# BLE_v0_1a_prater_mod.net
KiCad netlist of a schematic drawn in EAGLE
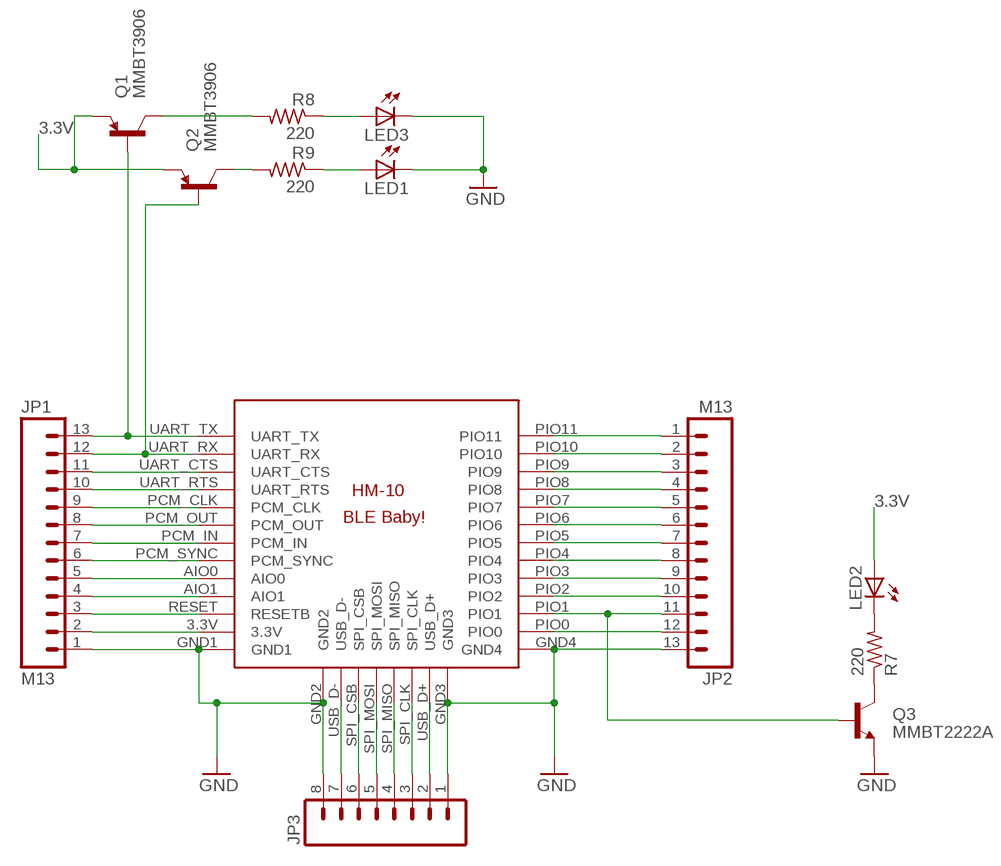
[diagram p0: schematic, sheet 1]

(export (version "E")
  (design (tool "Eeschema 10.0.6"))
  (components
    (comp (ref "JP1")
      (value "M13")
      (footprint "eagle-import:1X13")
      (libsource (lib "eagle-import") (part "M13"))
    )
    (comp (ref "JP2")
      (value "M13")
      (footprint "eagle-import:1X13")
      (libsource (lib "eagle-import") (part "M13"))
    )
    (comp (ref "JP3")
      (value "M081X08")
      (footprint "eagle-import:1X08")
      (libsource (lib "eagle-import") (part "M081X08"))
    )
    (comp (ref "LED1")
      (value "LED0603")
      (footprint "eagle-import:LED-0603")
      (libsource (lib "eagle-import") (part "LED0603"))
    )
    (comp (ref "LED2")
      (value "LED0603")
      (footprint "eagle-import:LED-0603")
      (libsource (lib "eagle-import") (part "LED0603"))
    )
    (comp (ref "LED3")
      (value "LED0603")
      (footprint "eagle-import:LED-0603")
      (libsource (lib "eagle-import") (part "LED0603"))
    )
    (comp (ref "Q1")
      (value "MMBT3906")
      (footprint "eagle-import:SOT23")
      (libsource (lib "eagle-import") (part "TRANSISTOR_PNPMMBT3906"))
    )
    (comp (ref "Q2")
      (value "MMBT3906")
      (footprint "eagle-import:SOT23")
      (libsource (lib "eagle-import") (part "TRANSISTOR_PNPMMBT3906"))
    )
    (comp (ref "Q3")
      (value "MMBT2222A")
      (footprint "eagle-import:SOT23")
      (libsource (lib "eagle-import") (part "TRANSISTOR_NPNMMBT2222A"))
    )
    (comp (ref "R7")
      (value "220")
      (footprint "eagle-import:M0805")
      (libsource (lib "eagle-import") (part "R-US_M0805"))
    )
    (comp (ref "R8")
      (value "220")
      (footprint "eagle-import:M0805")
      (libsource (lib "eagle-import") (part "R-US_M0805"))
    )
    (comp (ref "R9")
      (value "220")
      (footprint "eagle-import:M0805")
      (libsource (lib "eagle-import") (part "R-US_M0805"))
    )
    (comp (ref "U$1")
      (value "BLE-HM-10")
      (footprint "eagle-import:BLE-HM-10")
      (libsource (lib "eagle-import") (part "BLE-HM-10"))
    )
  )
  (nets
    (net (code "1") (name "/3.3V") (class "Default")
      (node (ref "LED2") (pin "A") (pinfunction "A_A") (pintype "passive"))
      (node (ref "Q1") (pin "2") (pinfunction "E_2") (pintype "passive"))
      (node (ref "Q2") (pin "2") (pinfunction "E_2") (pintype "passive"))
    )
    (net (code "2") (name "GND") (class "Default")
      (node (ref "JP1") (pin "1") (pinfunction "1_1") (pintype "passive"))
      (node (ref "JP2") (pin "13") (pinfunction "13_13") (pintype "passive"))
      (node (ref "JP3") (pin "1") (pinfunction "1_1") (pintype "passive"))
      (node (ref "JP3") (pin "8") (pinfunction "8_8") (pintype "passive"))
      (node (ref "LED1") (pin "C") (pinfunction "C_C") (pintype "passive"))
      (node (ref "LED3") (pin "C") (pinfunction "C_C") (pintype "passive"))
      (node (ref "Q3") (pin "2") (pinfunction "E_2") (pintype "passive"))
      (node (ref "U$1") (pin "GND1") (pinfunction "GND1_GND1") (pintype "bidirectional"))
      (node (ref "U$1") (pin "GND2") (pinfunction "GND2_GND2") (pintype "bidirectional"))
      (node (ref "U$1") (pin "GND3") (pinfunction "GND3_GND3") (pintype "bidirectional"))
      (node (ref "U$1") (pin "GND4") (pinfunction "GND4_GND4") (pintype "bidirectional"))
    )
    (net (code "3") (name "Net-(JP1-Pad2)") (class "Default")
      (node (ref "JP1") (pin "2") (pinfunction "2_2") (pintype "passive"))
      (node (ref "U$1") (pin "3.3V") (pinfunction "3.3V_3.3V") (pintype "bidirectional"))
    )
    (net (code "4") (name "Net-(JP1-Pad4)") (class "Default")
      (node (ref "JP1") (pin "4") (pinfunction "4_4") (pintype "passive"))
      (node (ref "U$1") (pin "AIO1") (pinfunction "AIO1_AIO1") (pintype "bidirectional"))
    )
    (net (code "5") (name "Net-(JP1-Pad5)") (class "Default")
      (node (ref "JP1") (pin "5") (pinfunction "5_5") (pintype "passive"))
      (node (ref "U$1") (pin "AIO0") (pinfunction "AIO0_AIO0") (pintype "bidirectional"))
    )
    (net (code "6") (name "Net-(JP1-Pad6)") (class "Default")
      (node (ref "JP1") (pin "6") (pinfunction "6_6") (pintype "passive"))
      (node (ref "U$1") (pin "PCM_SYNC") (pinfunction "PCM_SYNC_PCM_SYNC") (pintype "bidirectional"))
    )
    (net (code "7") (name "Net-(JP1-Pad7)") (class "Default")
      (node (ref "JP1") (pin "7") (pinfunction "7_7") (pintype "passive"))
      (node (ref "U$1") (pin "PCM_IN") (pinfunction "PCM_IN_PCM_IN") (pintype "bidirectional"))
    )
    (net (code "8") (name "Net-(JP1-Pad8)") (class "Default")
      (node (ref "JP1") (pin "8") (pinfunction "8_8") (pintype "passive"))
      (node (ref "U$1") (pin "PCM_OUT") (pinfunction "PCM_OUT_PCM_OUT") (pintype "bidirectional"))
    )
    (net (code "9") (name "Net-(JP1-Pad9)") (class "Default")
      (node (ref "JP1") (pin "9") (pinfunction "9_9") (pintype "passive"))
      (node (ref "U$1") (pin "PCM_CLK") (pinfunction "PCM_CLK_PCM_CLK") (pintype "bidirectional"))
    )
    (net (code "10") (name "Net-(JP1-Pad10)") (class "Default")
      (node (ref "JP1") (pin "10") (pinfunction "10_10") (pintype "passive"))
      (node (ref "U$1") (pin "UART_RTS") (pinfunction "UART_RTS_UART_RTS") (pintype "bidirectional"))
    )
    (net (code "11") (name "Net-(JP1-Pad11)") (class "Default")
      (node (ref "JP1") (pin "11") (pinfunction "11_11") (pintype "passive"))
      (node (ref "U$1") (pin "UART_CTS") (pinfunction "UART_CTS_UART_CTS") (pintype "bidirectional"))
    )
    (net (code "12") (name "Net-(JP2-Pad1)") (class "Default")
      (node (ref "JP2") (pin "1") (pinfunction "1_1") (pintype "passive"))
      (node (ref "U$1") (pin "PIO11") (pinfunction "PIO11_PIO11") (pintype "bidirectional"))
    )
    (net (code "13") (name "Net-(JP2-Pad2)") (class "Default")
      (node (ref "JP2") (pin "2") (pinfunction "2_2") (pintype "passive"))
      (node (ref "U$1") (pin "PIO10") (pinfunction "PIO10_PIO10") (pintype "bidirectional"))
    )
    (net (code "14") (name "Net-(JP2-Pad3)") (class "Default")
      (node (ref "JP2") (pin "3") (pinfunction "3_3") (pintype "passive"))
      (node (ref "U$1") (pin "PIO9") (pinfunction "PIO9_PIO9") (pintype "bidirectional"))
    )
    (net (code "15") (name "Net-(JP2-Pad4)") (class "Default")
      (node (ref "JP2") (pin "4") (pinfunction "4_4") (pintype "passive"))
      (node (ref "U$1") (pin "PIO8") (pinfunction "PIO8_PIO8") (pintype "bidirectional"))
    )
    (net (code "16") (name "Net-(JP2-Pad5)") (class "Default")
      (node (ref "JP2") (pin "5") (pinfunction "5_5") (pintype "passive"))
      (node (ref "U$1") (pin "PIO7") (pinfunction "PIO7_PIO7") (pintype "bidirectional"))
    )
    (net (code "17") (name "Net-(JP2-Pad6)") (class "Default")
      (node (ref "JP2") (pin "6") (pinfunction "6_6") (pintype "passive"))
      (node (ref "U$1") (pin "PIO6") (pinfunction "PIO6_PIO6") (pintype "bidirectional"))
    )
    (net (code "18") (name "Net-(JP2-Pad7)") (class "Default")
      (node (ref "JP2") (pin "7") (pinfunction "7_7") (pintype "passive"))
      (node (ref "U$1") (pin "PIO5") (pinfunction "PIO5_PIO5") (pintype "bidirectional"))
    )
    (net (code "19") (name "Net-(JP2-Pad8)") (class "Default")
      (node (ref "JP2") (pin "8") (pinfunction "8_8") (pintype "passive"))
      (node (ref "U$1") (pin "PIO4") (pinfunction "PIO4_PIO4") (pintype "bidirectional"))
    )
    (net (code "20") (name "Net-(JP2-Pad9)") (class "Default")
      (node (ref "JP2") (pin "9") (pinfunction "9_9") (pintype "passive"))
      (node (ref "U$1") (pin "PIO3") (pinfunction "PIO3_PIO3") (pintype "bidirectional"))
    )
    (net (code "21") (name "Net-(JP2-Pad10)") (class "Default")
      (node (ref "JP2") (pin "10") (pinfunction "10_10") (pintype "passive"))
      (node (ref "U$1") (pin "PIO2") (pinfunction "PIO2_PIO2") (pintype "bidirectional"))
    )
    (net (code "22") (name "Net-(JP2-Pad12)") (class "Default")
      (node (ref "JP2") (pin "12") (pinfunction "12_12") (pintype "passive"))
      (node (ref "U$1") (pin "PIO0") (pinfunction "PIO0_PIO0") (pintype "bidirectional"))
    )
    (net (code "23") (name "Net-(JP3-Pad2)") (class "Default")
      (node (ref "JP3") (pin "2") (pinfunction "2_2") (pintype "passive"))
      (node (ref "U$1") (pin "USB_D+") (pinfunction "USB_D+_USB_D+") (pintype "bidirectional"))
    )
    (net (code "24") (name "Net-(JP3-Pad3)") (class "Default")
      (node (ref "JP3") (pin "3") (pinfunction "3_3") (pintype "passive"))
      (node (ref "U$1") (pin "SPI_CLK") (pinfunction "SPI_CLK_SPI_CLK") (pintype "bidirectional"))
    )
    (net (code "25") (name "Net-(JP3-Pad4)") (class "Default")
      (node (ref "JP3") (pin "4") (pinfunction "4_4") (pintype "passive"))
      (node (ref "U$1") (pin "SPI_MISO") (pinfunction "SPI_MISO_SPI_MISO") (pintype "bidirectional"))
    )
    (net (code "26") (name "Net-(JP3-Pad5)") (class "Default")
      (node (ref "JP3") (pin "5") (pinfunction "5_5") (pintype "passive"))
      (node (ref "U$1") (pin "SPI_MOSI") (pinfunction "SPI_MOSI_SPI_MOSI") (pintype "bidirectional"))
    )
    (net (code "27") (name "Net-(JP3-Pad6)") (class "Default")
      (node (ref "JP3") (pin "6") (pinfunction "6_6") (pintype "passive"))
      (node (ref "U$1") (pin "SPI_CSB") (pinfunction "SPI_CSB_SPI_CSB") (pintype "bidirectional"))
    )
    (net (code "28") (name "Net-(JP3-Pad7)") (class "Default")
      (node (ref "JP3") (pin "7") (pinfunction "7_7") (pintype "passive"))
      (node (ref "U$1") (pin "USB_D-") (pinfunction "USB_D-_USB_D-") (pintype "bidirectional"))
    )
    (net (code "29") (name "Net-(LED1-PadA)") (class "Default")
      (node (ref "LED1") (pin "A") (pinfunction "A_A") (pintype "passive"))
      (node (ref "R9") (pin "1") (pinfunction "1_1") (pintype "passive"))
    )
    (net (code "30") (name "Net-(LED2-PadC)") (class "Default")
      (node (ref "LED2") (pin "C") (pinfunction "C_C") (pintype "passive"))
      (node (ref "R7") (pin "2") (pinfunction "2_2") (pintype "passive"))
    )
    (net (code "31") (name "Net-(LED3-PadA)") (class "Default")
      (node (ref "LED3") (pin "A") (pinfunction "A_A") (pintype "passive"))
      (node (ref "R8") (pin "1") (pinfunction "1_1") (pintype "passive"))
    )
    (net (code "32") (name "Net-(Q1-B)") (class "Default")
      (node (ref "JP1") (pin "13") (pinfunction "13_13") (pintype "passive"))
      (node (ref "Q1") (pin "1") (pinfunction "B_1") (pintype "passive"))
      (node (ref "U$1") (pin "UART_TX") (pinfunction "UART_TX_UART_TX") (pintype "bidirectional"))
    )
    (net (code "33") (name "Net-(Q1-C)") (class "Default")
      (node (ref "Q1") (pin "3") (pinfunction "C_3") (pintype "passive"))
      (node (ref "R8") (pin "2") (pinfunction "2_2") (pintype "passive"))
    )
    (net (code "34") (name "Net-(Q2-B)") (class "Default")
      (node (ref "JP1") (pin "12") (pinfunction "12_12") (pintype "passive"))
      (node (ref "Q2") (pin "1") (pinfunction "B_1") (pintype "passive"))
      (node (ref "U$1") (pin "UART_RX") (pinfunction "UART_RX_UART_RX") (pintype "bidirectional"))
    )
    (net (code "35") (name "Net-(Q2-C)") (class "Default")
      (node (ref "Q2") (pin "3") (pinfunction "C_3") (pintype "passive"))
      (node (ref "R9") (pin "2") (pinfunction "2_2") (pintype "passive"))
    )
    (net (code "36") (name "Net-(Q3-B)") (class "Default")
      (node (ref "JP2") (pin "11") (pinfunction "11_11") (pintype "passive"))
      (node (ref "Q3") (pin "1") (pinfunction "B_1") (pintype "passive"))
      (node (ref "U$1") (pin "PIO1") (pinfunction "PIO1_PIO1") (pintype "bidirectional"))
    )
    (net (code "37") (name "Net-(Q3-C)") (class "Default")
      (node (ref "Q3") (pin "3") (pinfunction "C_3") (pintype "passive"))
      (node (ref "R7") (pin "1") (pinfunction "1_1") (pintype "passive"))
    )
    (net (code "38") (name "Net-(U$1-RESETB)") (class "Default")
      (node (ref "JP1") (pin "3") (pinfunction "3_3") (pintype "passive"))
      (node (ref "U$1") (pin "RESET") (pinfunction "RESETB_RESET") (pintype "bidirectional"))
    )
  )
)
